# TOP.net
KiCad netlist of a schematic drawn in Altium Designer
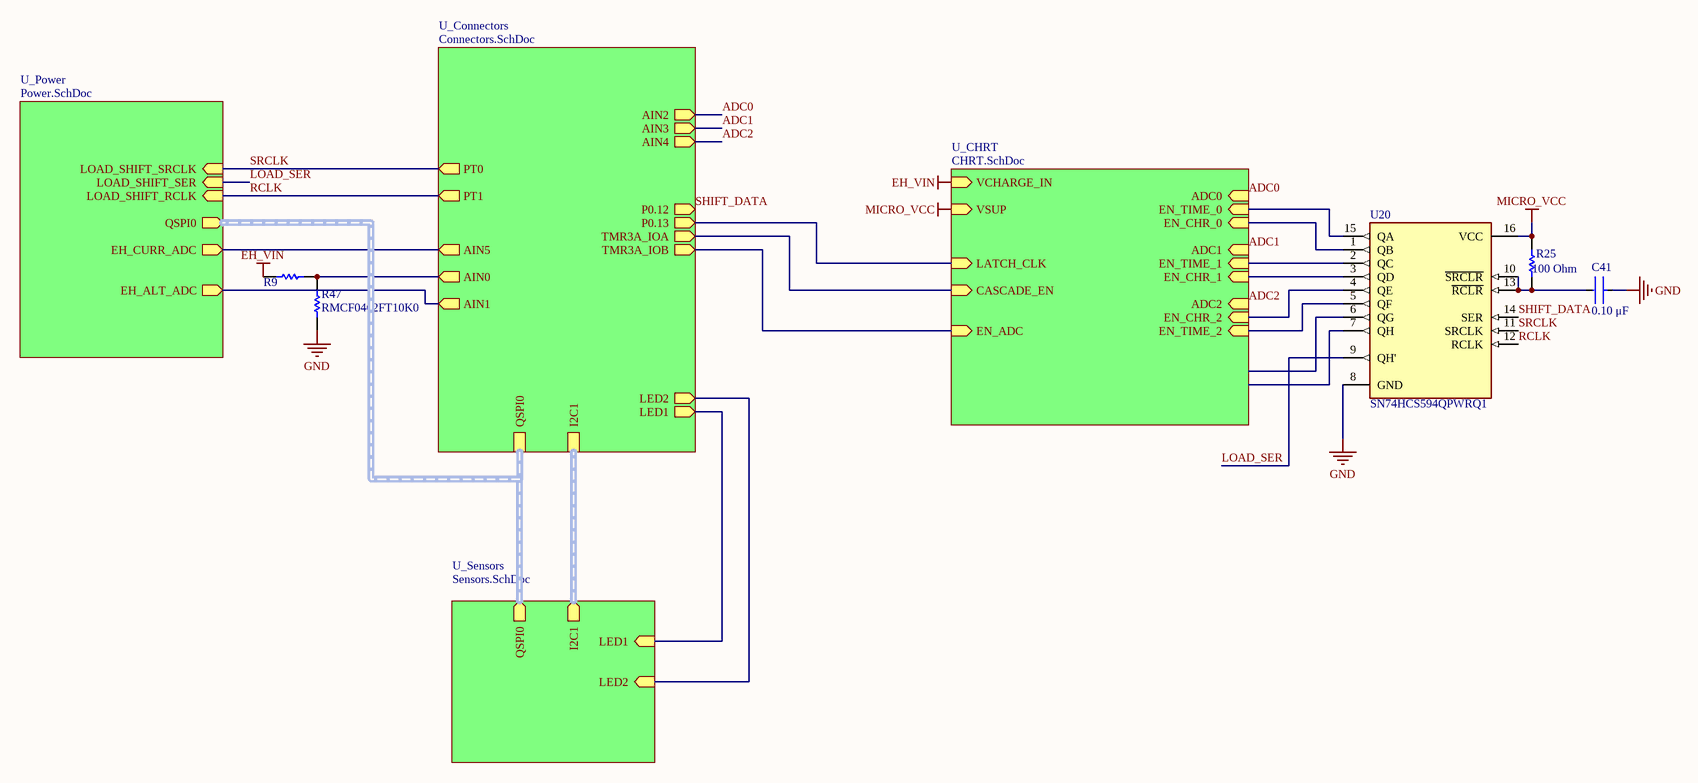
[diagram p0: TOP.SchDoc]

(export (version "E")
  (design (tool "Eeschema 10.0.6"))
  (components
    (comp (ref "C41")
      (value "C0402C104K8PACTU")
      (footprint "FP-C0402-BB-MFG")
      (description "CAP CER 0.1UF 10V X5R 0402")
      (fields
        (field (name "CAPACITANCE") "0.10 μF")
        (field (name "MANUFACTURER") "Kemet")
        (field (name "TOLERANCE") "0.1")
      )
      (libsource (lib "Altium Content Vault") (part "b4654b650e69147ec39a6b967a45e02"))
    )
    (comp (ref "R9")
      (value "RC0402JR-075M6L")
      (footprint "RESC1005X40X25ML05T10")
      (fields (field (name "MANUFACTURER") "Yageo / Phycomp"))
      (libsource (lib "Altium Content Vault") (part "RES"))
    )
    (comp (ref "R25")
      (value "ERJ-2RKF1000X")
      (footprint "RESC1005X40X25LL05T05")
      (description "Chip Resistor, 100 Ohm, +/- 1%, 100 mW, -55 to 155 degC, 0402 (1005 Metric), RoHS, Tape and Reel")
      (fields
        (field (name "MANUFACTURER") "Basic Passives")
        (field (name "TOLERANCE") "1%")
        (field (name "RESISTANCE") "100 Ohm")
      )
      (libsource (lib "Altium Content Vault") (part "RES-2"))
    )
    (comp (ref "R47")
      (value "RMCF0402FT10K0")
      (footprint "RESC1005X40X25ML05T10")
      (fields (field (name "MANUFACTURER") "Yageo / Phycomp") (field (name "PART NUMBER") "RC0402FR-071ML"))
      (libsource (lib "Altium Content Vault") (part "RES"))
    )
    (comp (ref "U20")
      (value "SN74HCS594QPWRQ1")
      (footprint "FP-PW0016A-IPC_A")
      (description "AUTOMOTIVE 8-BIT SHIFT REGISTERS")
      (libsource (lib "Altium Content Vault") (part "ee4c9120f52ff91501c7aa2bff67eb2"))
    )
  )
  (nets
    (net (code "4") (name "/AIN0") (class "Default")
      (node (ref "R47") (pin "2") (pinfunction "2_2") (pintype "passive"))
      (node (ref "R9") (pin "2") (pinfunction "2_2") (pintype "passive"))
    )
    (net (code "7") (name "/EN_CHR_0") (class "Default")
      (node (ref "U20") (pin "1") (pinfunction "QB_1") (pintype "output"))
    )
    (net (code "8") (name "/EN_CHR_1") (class "Default")
      (node (ref "U20") (pin "3") (pinfunction "QD_3") (pintype "output"))
    )
    (net (code "9") (name "/EN_CHR_2") (class "Default")
      (node (ref "U20") (pin "4") (pinfunction "QE_4") (pintype "output"))
    )
    (net (code "10") (name "/EN_TIME_0") (class "Default")
      (node (ref "U20") (pin "15") (pinfunction "QA_15") (pintype "output"))
    )
    (net (code "11") (name "/EN_TIME_1") (class "Default")
      (node (ref "U20") (pin "2") (pinfunction "QC_2") (pintype "output"))
    )
    (net (code "12") (name "/EN_TIME_2") (class "Default")
      (node (ref "U20") (pin "5") (pinfunction "QF_5") (pintype "output"))
    )
    (net (code "16") (name "/LOAD_SER") (class "Default")
      (node (ref "U20") (pin "9") (pinfunction "QH'_9") (pintype "output"))
    )
    (net (code "19") (name "/RCLK") (class "Default")
      (node (ref "U20") (pin "12") (pinfunction "RCLK_12") (pintype "input"))
    )
    (net (code "20") (name "/SHIFT_DATA") (class "Default")
      (node (ref "U20") (pin "14") (pinfunction "SER_14") (pintype "input"))
    )
    (net (code "21") (name "/SRCLK") (class "Default")
      (node (ref "U20") (pin "11") (pinfunction "SRCLK_11") (pintype "input"))
    )
    (net (code "24") (name "EH_VIN") (class "Default")
      (node (ref "R9") (pin "1") (pinfunction "1_1") (pintype "passive"))
    )
    (net (code "25") (name "GND") (class "Default")
      (node (ref "C41") (pin "1") (pinfunction "1_1") (pintype "passive"))
      (node (ref "R47") (pin "1") (pinfunction "1_1") (pintype "passive"))
      (node (ref "U20") (pin "8") (pinfunction "GND_8") (pintype "power_in"))
    )
    (net (code "26") (name "MICRO_VCC") (class "Default")
      (node (ref "R25") (pin "2") (pinfunction "2_2") (pintype "passive"))
      (node (ref "U20") (pin "16") (pinfunction "VCC_16") (pintype "power_in"))
    )
    (net (code "27") (name "Net-(U20-~{RCLR})") (class "Default")
      (node (ref "C41") (pin "2") (pinfunction "2_2") (pintype "passive"))
      (node (ref "R25") (pin "1") (pinfunction "1_1") (pintype "passive"))
      (node (ref "U20") (pin "10") (pinfunction "~{SRCLR}_10") (pintype "input"))
      (node (ref "U20") (pin "13") (pinfunction "~{RCLR}_13") (pintype "input"))
    )
    (net (code "28") (name "unconnected-(U20-QG-Pad6)") (class "Default")
      (node (ref "U20") (pin "6") (pinfunction "QG_6") (pintype "output"))
    )
    (net (code "29") (name "unconnected-(U20-QH-Pad7)") (class "Default")
      (node (ref "U20") (pin "7") (pinfunction "QH_7") (pintype "output"))
    )
  )
)
